# Analog.net
KiCad netlist of a schematic drawn in Altium Designer
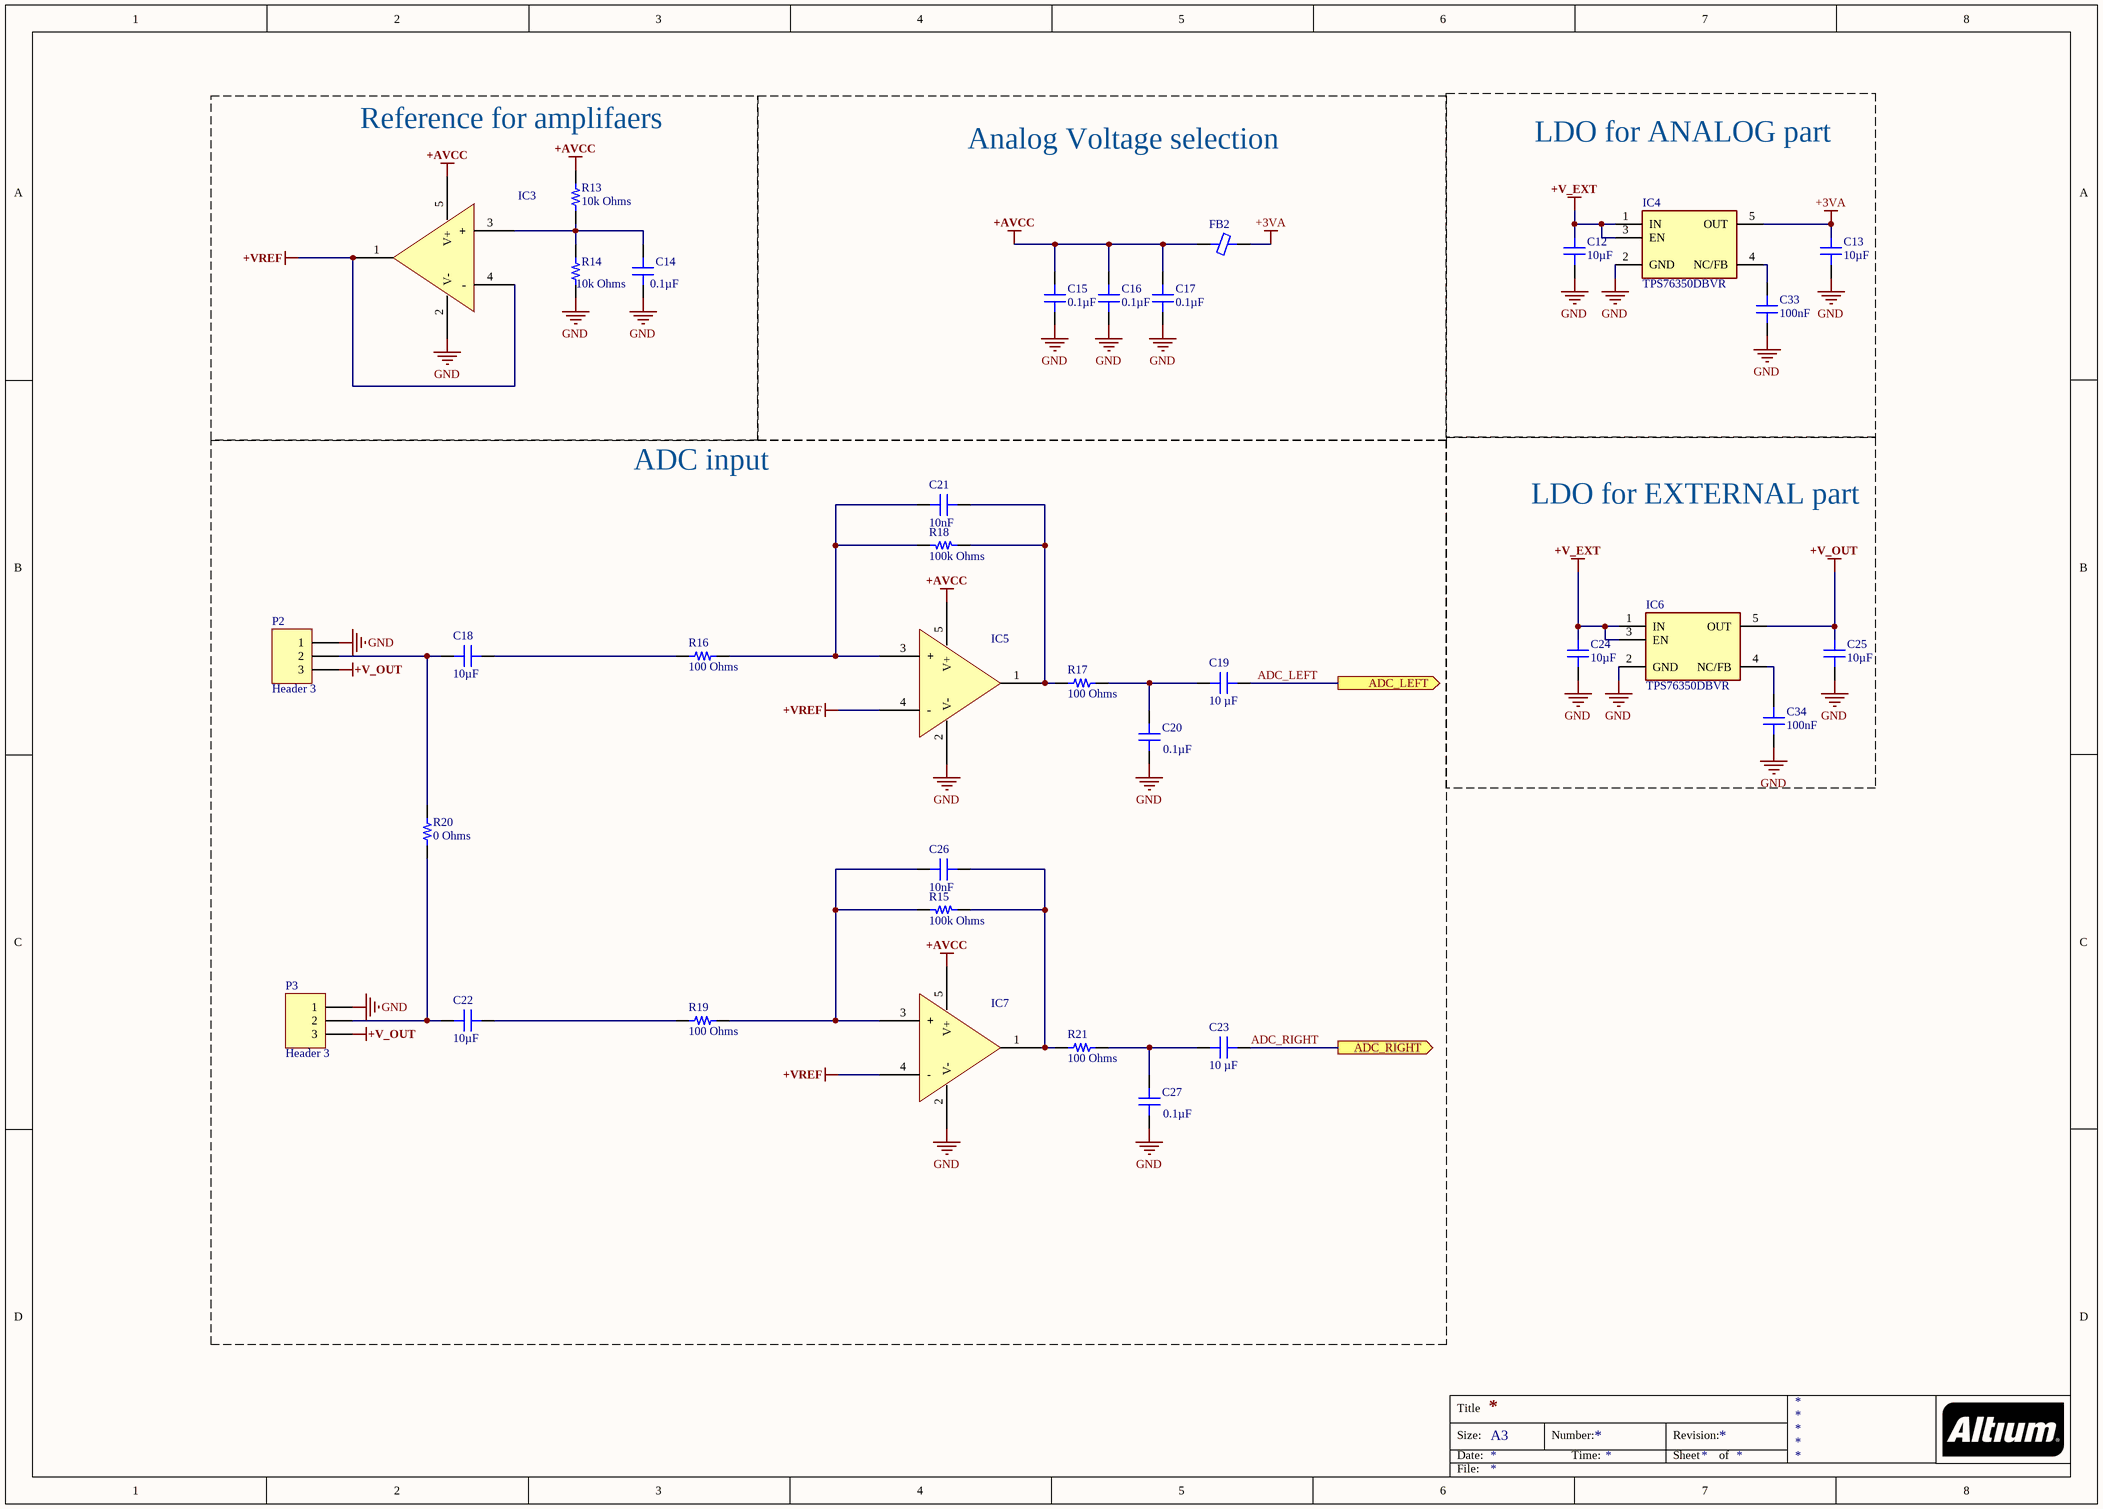
[diagram p0: Analog.SchDoc]

(export (version "E")
  (design (tool "Eeschema 10.0.6"))
  (components
    (comp (ref "C12")
      (value "10µF")
      (footprint "CAP 0603_1608")
      (description "CAP CER 0.1UF 10V X7R 0603")
      (fields (field (name "PART NUMBER") "100X14W104MV4T"))
      (libsource (lib "Celestial Altium Library - altium_library") (part "Capacitor"))
    )
    (comp (ref "C13")
      (value "10µF")
      (footprint "CAP 0603_1608")
      (description "CAP CER 0.1UF 10V X7R 0603")
      (fields (field (name "PART NUMBER") "100X14W104MV4T"))
      (libsource (lib "Celestial Altium Library - altium_library") (part "Capacitor"))
    )
    (comp (ref "C14")
      (value "0.1µF")
      (footprint "CAP 0603_1608")
      (description "CAP CER 0.1UF 10V X7R 0603")
      (fields (field (name "PART NUMBER") "100X14W104MV4T"))
      (libsource (lib "Celestial Altium Library - altium_library") (part "Capacitor"))
    )
    (comp (ref "C15")
      (value "0.1µF")
      (footprint "CAP 0603_1608")
      (description "CAP CER 0.1UF 10V X7R 0603")
      (fields (field (name "PART NUMBER") "100X14W104MV4T"))
      (libsource (lib "Celestial Altium Library - altium_library") (part "Capacitor"))
    )
    (comp (ref "C16")
      (value "0.1µF")
      (footprint "CAP 0603_1608")
      (description "CAP CER 0.1UF 10V X7R 0603")
      (fields (field (name "PART NUMBER") "100X14W104MV4T"))
      (libsource (lib "Celestial Altium Library - altium_library") (part "Capacitor"))
    )
    (comp (ref "C17")
      (value "0.1µF")
      (footprint "CAP 0603_1608")
      (description "CAP CER 0.1UF 10V X7R 0603")
      (fields (field (name "PART NUMBER") "100X14W104MV4T"))
      (libsource (lib "Celestial Altium Library - altium_library") (part "Capacitor"))
    )
    (comp (ref "C18")
      (value "10µF")
      (footprint "CAP 0603_1608")
      (description "CAP CER 0.1UF 10V X7R 0603")
      (fields (field (name "PART NUMBER") "100X14W104MV4T"))
      (libsource (lib "Celestial Altium Library - altium_library") (part "Capacitor"))
    )
    (comp (ref "C19")
      (value "10 µF")
      (footprint "CAP 0603_1608")
      (description "CAP CER 0.1UF 10V X7R 0603")
      (fields (field (name "PART NUMBER") "100X14W104MV4T"))
      (libsource (lib "Celestial Altium Library - altium_library") (part "Capacitor"))
    )
    (comp (ref "C20")
      (value "0.1µF")
      (footprint "CAP 0603_1608")
      (description "CAP CER 0.1UF 10V X7R 0603")
      (fields (field (name "PART NUMBER") "100X14W104MV4T"))
      (libsource (lib "Celestial Altium Library - altium_library") (part "Capacitor"))
    )
    (comp (ref "C21")
      (value "10nF")
      (footprint "CAP 0603_1608")
      (description "CAP CER 0.1UF 10V X7R 0603")
      (fields (field (name "PART NUMBER") "100X14W104MV4T"))
      (libsource (lib "Celestial Altium Library - altium_library") (part "Capacitor"))
    )
    (comp (ref "C22")
      (value "10µF")
      (footprint "CAP 0603_1608")
      (description "CAP CER 0.1UF 10V X7R 0603")
      (fields (field (name "PART NUMBER") "100X14W104MV4T"))
      (libsource (lib "Celestial Altium Library - altium_library") (part "Capacitor"))
    )
    (comp (ref "C23")
      (value "10 µF")
      (footprint "CAP 0603_1608")
      (description "CAP CER 0.1UF 10V X7R 0603")
      (fields (field (name "PART NUMBER") "100X14W104MV4T"))
      (libsource (lib "Celestial Altium Library - altium_library") (part "Capacitor"))
    )
    (comp (ref "C24")
      (value "10µF")
      (footprint "CAP 0603_1608")
      (description "CAP CER 0.1UF 10V X7R 0603")
      (fields (field (name "PART NUMBER") "100X14W104MV4T"))
      (libsource (lib "Celestial Altium Library - altium_library") (part "Capacitor"))
    )
    (comp (ref "C25")
      (value "10µF")
      (footprint "CAP 0603_1608")
      (description "CAP CER 0.1UF 10V X7R 0603")
      (fields (field (name "PART NUMBER") "100X14W104MV4T"))
      (libsource (lib "Celestial Altium Library - altium_library") (part "Capacitor"))
    )
    (comp (ref "C26")
      (value "10nF")
      (footprint "CAP 0603_1608")
      (description "CAP CER 0.1UF 10V X7R 0603")
      (fields (field (name "PART NUMBER") "100X14W104MV4T"))
      (libsource (lib "Celestial Altium Library - altium_library") (part "Capacitor"))
    )
    (comp (ref "C27")
      (value "0.1µF")
      (footprint "CAP 0603_1608")
      (description "CAP CER 0.1UF 10V X7R 0603")
      (fields (field (name "PART NUMBER") "100X14W104MV4T"))
      (libsource (lib "Celestial Altium Library - altium_library") (part "Capacitor"))
    )
    (comp (ref "C33")
      (value "100nF")
      (footprint "CAP 0603_1608")
      (description "CAP CER 0.1UF 10V X7R 0603")
      (fields (field (name "PART NUMBER") "100X14W104MV4T"))
      (libsource (lib "Celestial Altium Library - altium_library") (part "Capacitor"))
    )
    (comp (ref "C34")
      (value "100nF")
      (footprint "CAP 0603_1608")
      (description "CAP CER 0.1UF 10V X7R 0603")
      (fields (field (name "PART NUMBER") "100X14W104MV4T"))
      (libsource (lib "Celestial Altium Library - altium_library") (part "Capacitor"))
    )
    (comp (ref "FB2")
      (value "~")
      (footprint "FER 0603_1608")
      (description "FERRITE BEAD 0603 1LN")
      (fields (field (name "PART NUMBER") "2506031217H0"))
      (libsource (lib "Celestial Altium Library - altium_library") (part "Ferrite Chip"))
    )
    (comp (ref "IC3")
      (value "AD8541ARTZ-REEL7")
      (footprint "ANALOG SOT-23-5 RJ-5")
      (description "IC OPAMP GP 1 CIRCUIT SOT23-5")
      (fields (field (name "MANUFACTURER") "Analog Devices Inc."))
      (libsource (lib "Celestial Altium Library - altium_library") (part "ANALOG DEV AD8541 KS-RJ"))
    )
    (comp (ref "IC4")
      (value "TPS76350DBVR")
      (footprint "SamacSys:SOT95P280X145-5N")
      (description "Integrated Circuit")
      (fields (field (name "MOUSER PART NUMBER") "595-TPS76350DBVR"))
      (libsource (lib "SamacSys") (part "TPS76350DBVR"))
    )
    (comp (ref "IC5")
      (value "AD8541ARTZ-REEL7")
      (footprint "ANALOG SOT-23-5 RJ-5")
      (description "IC OPAMP GP 1 CIRCUIT SOT23-5")
      (fields (field (name "MANUFACTURER") "Analog Devices Inc."))
      (libsource (lib "Celestial Altium Library - altium_library") (part "ANALOG DEV AD8541 KS-RJ"))
    )
    (comp (ref "IC6")
      (value "TPS76350DBVR")
      (footprint "SamacSys:SOT95P280X145-5N")
      (description "Integrated Circuit")
      (fields (field (name "MOUSER PART NUMBER") "595-TPS76350DBVR"))
      (libsource (lib "SamacSys") (part "TPS76350DBVR"))
    )
    (comp (ref "IC7")
      (value "AD8541ARTZ-REEL7")
      (footprint "ANALOG SOT-23-5 RJ-5")
      (description "IC OPAMP GP 1 CIRCUIT SOT23-5")
      (fields (field (name "MANUFACTURER") "Analog Devices Inc."))
      (libsource (lib "Celestial Altium Library - altium_library") (part "ANALOG DEV AD8541 KS-RJ"))
    )
    (comp (ref "P2")
      (value "Header 3")
      (footprint "HDR1X3")
      (description "Header, 3-Pin")
      (fields (field (name "PUBLISHER") "Altium Limited"))
      (libsource (lib "Miscellaneous Connectors") (part "Header 3"))
    )
    (comp (ref "P3")
      (value "Header 3")
      (footprint "HDR1X3")
      (description "Header, 3-Pin")
      (fields (field (name "PUBLISHER") "Altium Limited"))
      (libsource (lib "Miscellaneous Connectors") (part "Header 3"))
    )
    (comp (ref "R13")
      (value "10k Ohms")
      (footprint "RES 0603_1608")
      (description "RES 100 OHM 0.1% 1/16W 0603")
      (fields (field (name "PART NUMBER") "RNCS0603BKE100R"))
      (libsource (lib "Celestial Altium Library - altium_library") (part "Resistor"))
    )
    (comp (ref "R14")
      (value "10k Ohms")
      (footprint "RES 0603_1608")
      (description "RES 100 OHM 0.1% 1/16W 0603")
      (fields (field (name "PART NUMBER") "RNCS0603BKE100R"))
      (libsource (lib "Celestial Altium Library - altium_library") (part "Resistor"))
    )
    (comp (ref "R15")
      (value "100k Ohms")
      (footprint "RES 0603_1608")
      (description "RES 100 OHM 0.1% 1/16W 0603")
      (fields (field (name "PART NUMBER") "RNCS0603BKE100R"))
      (libsource (lib "Celestial Altium Library - altium_library") (part "Resistor"))
    )
    (comp (ref "R16")
      (value "100 Ohms")
      (footprint "RES 0603_1608")
      (description "RES 100 OHM 0.1% 1/16W 0603")
      (fields (field (name "PART NUMBER") "RNCS0603BKE100R"))
      (libsource (lib "Celestial Altium Library - altium_library") (part "Resistor"))
    )
    (comp (ref "R17")
      (value "100 Ohms")
      (footprint "RES 0603_1608")
      (description "RES 100 OHM 0.1% 1/16W 0603")
      (fields (field (name "PART NUMBER") "RNCS0603BKE100R"))
      (libsource (lib "Celestial Altium Library - altium_library") (part "Resistor"))
    )
    (comp (ref "R18")
      (value "100k Ohms")
      (footprint "RES 0603_1608")
      (description "RES 100 OHM 0.1% 1/16W 0603")
      (fields (field (name "PART NUMBER") "RNCS0603BKE100R"))
      (libsource (lib "Celestial Altium Library - altium_library") (part "Resistor"))
    )
    (comp (ref "R19")
      (value "100 Ohms")
      (footprint "RES 0603_1608")
      (description "RES 100 OHM 0.1% 1/16W 0603")
      (fields (field (name "PART NUMBER") "RNCS0603BKE100R"))
      (libsource (lib "Celestial Altium Library - altium_library") (part "Resistor"))
    )
    (comp (ref "R20")
      (value "0 Ohms")
      (footprint "RES 0603_1608")
      (description "RES 100 OHM 0.1% 1/16W 0603")
      (fields (field (name "PART NUMBER") "RNCS0603BKE100R"))
      (libsource (lib "Celestial Altium Library - altium_library") (part "Resistor"))
    )
    (comp (ref "R21")
      (value "100 Ohms")
      (footprint "RES 0603_1608")
      (description "RES 100 OHM 0.1% 1/16W 0603")
      (fields (field (name "PART NUMBER") "RNCS0603BKE100R"))
      (libsource (lib "Celestial Altium Library - altium_library") (part "Resistor"))
    )
  )
  (nets
    (net (code "1") (name "+3VA") (class "Default")
      (node (ref "C13") (pin "2") (pinfunction "2_2") (pintype "passive"))
      (node (ref "FB2") (pin "2") (pinfunction "2_2") (pintype "passive"))
      (node (ref "IC4") (pin "5") (pinfunction "OUT_5") (pintype "passive"))
    )
    (net (code "2") (name "+AVCC") (class "Default")
      (node (ref "C15") (pin "2") (pinfunction "2_2") (pintype "passive"))
      (node (ref "C16") (pin "2") (pinfunction "2_2") (pintype "passive"))
      (node (ref "C17") (pin "2") (pinfunction "2_2") (pintype "passive"))
      (node (ref "FB2") (pin "1") (pinfunction "1_1") (pintype "passive"))
      (node (ref "IC3") (pin "5") (pinfunction "V+_5") (pintype "passive"))
      (node (ref "IC5") (pin "5") (pinfunction "V+_5") (pintype "passive"))
      (node (ref "IC7") (pin "5") (pinfunction "V+_5") (pintype "passive"))
      (node (ref "R13") (pin "2") (pinfunction "2_2") (pintype "passive"))
    )
    (net (code "3") (name "+VREF") (class "Default")
      (node (ref "IC3") (pin "1") (pinfunction "OUT_1") (pintype "passive"))
      (node (ref "IC3") (pin "4") (pinfunction "-_4") (pintype "passive"))
      (node (ref "IC5") (pin "4") (pinfunction "-_4") (pintype "passive"))
      (node (ref "IC7") (pin "4") (pinfunction "-_4") (pintype "passive"))
    )
    (net (code "4") (name "+V_EXT") (class "Default")
      (node (ref "C12") (pin "2") (pinfunction "2_2") (pintype "passive"))
      (node (ref "C24") (pin "2") (pinfunction "2_2") (pintype "passive"))
      (node (ref "IC4") (pin "1") (pinfunction "IN_1") (pintype "passive"))
      (node (ref "IC4") (pin "3") (pinfunction "EN_3") (pintype "passive"))
      (node (ref "IC6") (pin "1") (pinfunction "IN_1") (pintype "passive"))
      (node (ref "IC6") (pin "3") (pinfunction "EN_3") (pintype "passive"))
    )
    (net (code "5") (name "+V_OUT") (class "Default")
      (node (ref "C25") (pin "2") (pinfunction "2_2") (pintype "passive"))
      (node (ref "IC6") (pin "5") (pinfunction "OUT_5") (pintype "passive"))
      (node (ref "P2") (pin "3") (pinfunction "3_3") (pintype "passive"))
      (node (ref "P3") (pin "3") (pinfunction "3_3") (pintype "passive"))
    )
    (net (code "6") (name "/ADC_LEFT") (class "Default")
      (node (ref "C19") (pin "2") (pinfunction "2_2") (pintype "passive"))
    )
    (net (code "7") (name "/ADC_RIGHT") (class "Default")
      (node (ref "C23") (pin "2") (pinfunction "2_2") (pintype "passive"))
    )
    (net (code "8") (name "GND") (class "Default")
      (node (ref "C12") (pin "1") (pinfunction "1_1") (pintype "passive"))
      (node (ref "C13") (pin "1") (pinfunction "1_1") (pintype "passive"))
      (node (ref "C14") (pin "1") (pinfunction "1_1") (pintype "passive"))
      (node (ref "C15") (pin "1") (pinfunction "1_1") (pintype "passive"))
      (node (ref "C16") (pin "1") (pinfunction "1_1") (pintype "passive"))
      (node (ref "C17") (pin "1") (pinfunction "1_1") (pintype "passive"))
      (node (ref "C20") (pin "1") (pinfunction "1_1") (pintype "passive"))
      (node (ref "C24") (pin "1") (pinfunction "1_1") (pintype "passive"))
      (node (ref "C25") (pin "1") (pinfunction "1_1") (pintype "passive"))
      (node (ref "C27") (pin "1") (pinfunction "1_1") (pintype "passive"))
      (node (ref "C33") (pin "1") (pinfunction "1_1") (pintype "passive"))
      (node (ref "C34") (pin "1") (pinfunction "1_1") (pintype "passive"))
      (node (ref "IC3") (pin "2") (pinfunction "V-_2") (pintype "passive"))
      (node (ref "IC4") (pin "2") (pinfunction "GND_2") (pintype "passive"))
      (node (ref "IC5") (pin "2") (pinfunction "V-_2") (pintype "passive"))
      (node (ref "IC6") (pin "2") (pinfunction "GND_2") (pintype "passive"))
      (node (ref "IC7") (pin "2") (pinfunction "V-_2") (pintype "passive"))
      (node (ref "P2") (pin "1") (pinfunction "1_1") (pintype "passive"))
      (node (ref "P3") (pin "1") (pinfunction "1_1") (pintype "passive"))
      (node (ref "R14") (pin "1") (pinfunction "1_1") (pintype "passive"))
    )
    (net (code "9") (name "Net-(C18-Pad1)") (class "Default")
      (node (ref "C18") (pin "1") (pinfunction "1_1") (pintype "passive"))
      (node (ref "R16") (pin "2") (pinfunction "2_2") (pintype "passive"))
    )
    (net (code "10") (name "Net-(C18-Pad2)") (class "Default")
      (node (ref "C18") (pin "2") (pinfunction "2_2") (pintype "passive"))
      (node (ref "P2") (pin "2") (pinfunction "2_2") (pintype "passive"))
      (node (ref "R20") (pin "1") (pinfunction "1_1") (pintype "passive"))
    )
    (net (code "11") (name "Net-(C19-Pad1)") (class "Default")
      (node (ref "C19") (pin "1") (pinfunction "1_1") (pintype "passive"))
      (node (ref "C20") (pin "2") (pinfunction "2_2") (pintype "passive"))
      (node (ref "R17") (pin "1") (pinfunction "1_1") (pintype "passive"))
    )
    (net (code "12") (name "Net-(C22-Pad1)") (class "Default")
      (node (ref "C22") (pin "1") (pinfunction "1_1") (pintype "passive"))
      (node (ref "R19") (pin "2") (pinfunction "2_2") (pintype "passive"))
    )
    (net (code "13") (name "Net-(C22-Pad2)") (class "Default")
      (node (ref "C22") (pin "2") (pinfunction "2_2") (pintype "passive"))
      (node (ref "P3") (pin "2") (pinfunction "2_2") (pintype "passive"))
      (node (ref "R20") (pin "2") (pinfunction "2_2") (pintype "passive"))
    )
    (net (code "14") (name "Net-(C23-Pad1)") (class "Default")
      (node (ref "C23") (pin "1") (pinfunction "1_1") (pintype "passive"))
      (node (ref "C27") (pin "2") (pinfunction "2_2") (pintype "passive"))
      (node (ref "R21") (pin "1") (pinfunction "1_1") (pintype "passive"))
    )
    (net (code "15") (name "Net-(IC3-+)") (class "Default")
      (node (ref "C14") (pin "2") (pinfunction "2_2") (pintype "passive"))
      (node (ref "IC3") (pin "3") (pinfunction "+_3") (pintype "passive"))
      (node (ref "R13") (pin "1") (pinfunction "1_1") (pintype "passive"))
      (node (ref "R14") (pin "2") (pinfunction "2_2") (pintype "passive"))
    )
    (net (code "16") (name "Net-(IC4-NC{slash}FB)") (class "Default")
      (node (ref "C33") (pin "2") (pinfunction "2_2") (pintype "passive"))
      (node (ref "IC4") (pin "4") (pinfunction "NC/FB_4") (pintype "passive"))
    )
    (net (code "17") (name "Net-(IC5-+)") (class "Default")
      (node (ref "C21") (pin "2") (pinfunction "2_2") (pintype "passive"))
      (node (ref "IC5") (pin "3") (pinfunction "+_3") (pintype "passive"))
      (node (ref "R16") (pin "1") (pinfunction "1_1") (pintype "passive"))
      (node (ref "R18") (pin "2") (pinfunction "2_2") (pintype "passive"))
    )
    (net (code "18") (name "Net-(IC5-OUT)") (class "Default")
      (node (ref "C21") (pin "1") (pinfunction "1_1") (pintype "passive"))
      (node (ref "IC5") (pin "1") (pinfunction "OUT_1") (pintype "passive"))
      (node (ref "R17") (pin "2") (pinfunction "2_2") (pintype "passive"))
      (node (ref "R18") (pin "1") (pinfunction "1_1") (pintype "passive"))
    )
    (net (code "19") (name "Net-(IC6-NC{slash}FB)") (class "Default")
      (node (ref "C34") (pin "2") (pinfunction "2_2") (pintype "passive"))
      (node (ref "IC6") (pin "4") (pinfunction "NC/FB_4") (pintype "passive"))
    )
    (net (code "20") (name "Net-(IC7-+)") (class "Default")
      (node (ref "C26") (pin "2") (pinfunction "2_2") (pintype "passive"))
      (node (ref "IC7") (pin "3") (pinfunction "+_3") (pintype "passive"))
      (node (ref "R15") (pin "2") (pinfunction "2_2") (pintype "passive"))
      (node (ref "R19") (pin "1") (pinfunction "1_1") (pintype "passive"))
    )
    (net (code "21") (name "Net-(IC7-OUT)") (class "Default")
      (node (ref "C26") (pin "1") (pinfunction "1_1") (pintype "passive"))
      (node (ref "IC7") (pin "1") (pinfunction "OUT_1") (pintype "passive"))
      (node (ref "R15") (pin "1") (pinfunction "1_1") (pintype "passive"))
      (node (ref "R21") (pin "2") (pinfunction "2_2") (pintype "passive"))
    )
  )
)
